# lightsensor.net
KiCad netlist of a schematic drawn in EAGLE
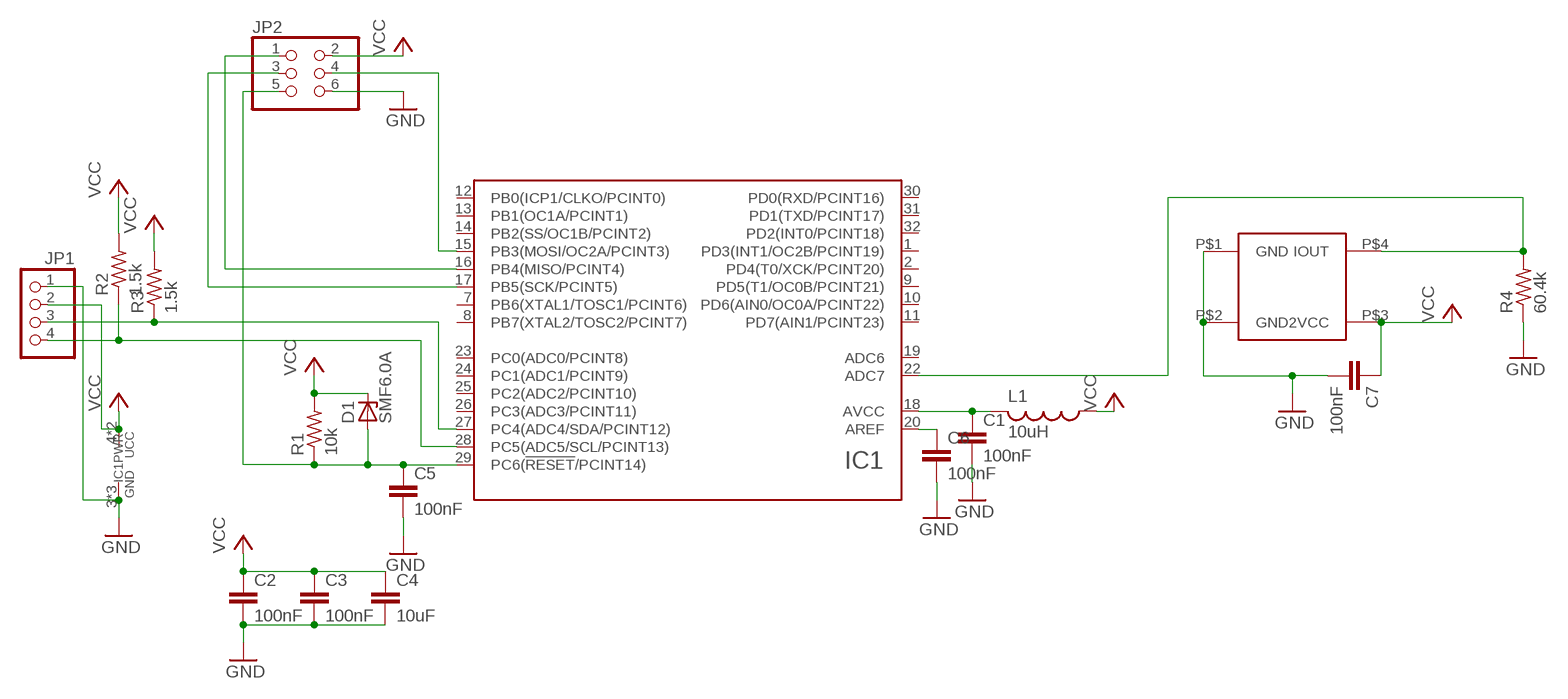
[diagram p0: schematic, sheet 1]

(export (version "E")
  (design (tool "Eeschema 10.0.6"))
  (components
    (comp (ref "C1")
      (value "100nF")
      (footprint "eagle-import:C0402")
      (libsource (lib "eagle-import") (part "C-EUC0402"))
    )
    (comp (ref "C2")
      (value "100nF")
      (footprint "eagle-import:C0402")
      (libsource (lib "eagle-import") (part "C-EUC0402"))
    )
    (comp (ref "C3")
      (value "100nF")
      (footprint "eagle-import:C0402")
      (libsource (lib "eagle-import") (part "C-EUC0402"))
    )
    (comp (ref "C4")
      (value "10uF")
      (footprint "eagle-import:C0603")
      (libsource (lib "eagle-import") (part "C-EUC0603"))
    )
    (comp (ref "C5")
      (value "100nF")
      (footprint "eagle-import:C0402")
      (libsource (lib "eagle-import") (part "C-EUC0402"))
    )
    (comp (ref "C6")
      (value "100nF")
      (footprint "eagle-import:C0402")
      (libsource (lib "eagle-import") (part "C-EUC0402"))
    )
    (comp (ref "C7")
      (value "100nF")
      (footprint "eagle-import:C0402")
      (libsource (lib "eagle-import") (part "C-EUC0402"))
    )
    (comp (ref "D1")
      (value "SMF6.0A")
      (footprint "eagle-import:SOD123F")
      (fields (field (name "MF") "Littelfuse"))
      (libsource (lib "eagle-import") (part "SMFA6.0"))
    )
    (comp (ref "IC1")
      (value "ATMEGA48/88/168/328-AU")
      (footprint "eagle-import:TQFP32-08")
      (libsource (lib "eagle-import") (part "ATMEGA48/88/168/328-AU"))
    )
    (comp (ref "JP1")
      (value "PINHD-1X4")
      (footprint "eagle-import:1X04")
      (libsource (lib "eagle-import") (part "PINHD-1X4"))
    )
    (comp (ref "JP2")
      (value "PINHD-2X3")
      (footprint "eagle-import:2X03")
      (libsource (lib "eagle-import") (part "PINHD-2X3"))
    )
    (comp (ref "L1")
      (value "10uH")
      (footprint "eagle-import:L2012C")
      (libsource (lib "eagle-import") (part "L-USL2012C"))
    )
    (comp (ref "R1")
      (value "10k")
      (footprint "eagle-import:R0402")
      (libsource (lib "eagle-import") (part "R-US_R0402"))
    )
    (comp (ref "R2")
      (value "1.5k")
      (footprint "eagle-import:R0402")
      (libsource (lib "eagle-import") (part "R-US_R0402"))
    )
    (comp (ref "R3")
      (value "1.5k")
      (footprint "eagle-import:R0402")
      (libsource (lib "eagle-import") (part "R-US_R0402"))
    )
    (comp (ref "R4")
      (value "60.4k")
      (footprint "eagle-import:R0603")
      (libsource (lib "eagle-import") (part "R-US_R0603"))
    )
    (comp (ref "U$1")
      (value "SFH5711")
      (footprint "eagle-import:SFH5711")
      (libsource (lib "eagle-import") (part "SFH5711"))
    )
  )
  (nets
    (net (code "1") (name "GND") (class "Default")
      (node (ref "C1") (pin "2") (pinfunction "2_2") (pintype "passive"))
      (node (ref "C2") (pin "2") (pinfunction "2_2") (pintype "passive"))
      (node (ref "C3") (pin "2") (pinfunction "2_2") (pintype "passive"))
      (node (ref "C4") (pin "2") (pinfunction "2_2") (pintype "passive"))
      (node (ref "C5") (pin "2") (pinfunction "2_2") (pintype "passive"))
      (node (ref "C6") (pin "2") (pinfunction "2_2") (pintype "passive"))
      (node (ref "C7") (pin "2") (pinfunction "2_2") (pintype "passive"))
      (node (ref "IC1") (pin "21") (pinfunction "GND_21") (pintype "power_in"))
      (node (ref "IC1") (pin "3") (pinfunction "GND_3") (pintype "power_in"))
      (node (ref "IC1") (pin "5") (pinfunction "GND_5") (pintype "power_in"))
      (node (ref "JP1") (pin "1") (pinfunction "1_1") (pintype "passive"))
      (node (ref "JP2") (pin "6") (pinfunction "6_6") (pintype "passive"))
      (node (ref "R4") (pin "1") (pinfunction "1_1") (pintype "passive"))
      (node (ref "U$1") (pin "P$1") (pinfunction "GND_P$1") (pintype "bidirectional"))
      (node (ref "U$1") (pin "P$2") (pinfunction "GND2_P$2") (pintype "bidirectional"))
    )
    (net (code "2") (name "Net-(IC1A-ADC7)") (class "Default")
      (node (ref "IC1") (pin "22") (pinfunction "ADC7_22") (pintype "passive"))
      (node (ref "R4") (pin "2") (pinfunction "2_2") (pintype "passive"))
      (node (ref "U$1") (pin "P$4") (pinfunction "IOUT_P$4") (pintype "bidirectional"))
    )
    (net (code "3") (name "Net-(IC1A-AREF)") (class "Default")
      (node (ref "C6") (pin "1") (pinfunction "1_1") (pintype "passive"))
      (node (ref "IC1") (pin "20") (pinfunction "AREF_20") (pintype "passive"))
    )
    (net (code "4") (name "Net-(IC1A-AVCC)") (class "Default")
      (node (ref "C1") (pin "1") (pinfunction "1_1") (pintype "passive"))
      (node (ref "IC1") (pin "18") (pinfunction "AVCC_18") (pintype "power_in"))
      (node (ref "L1") (pin "2") (pinfunction "2_2") (pintype "passive"))
    )
    (net (code "5") (name "Net-(IC1A-PB3(MOSI{slash}OC2A{slash}PCINT3))") (class "Default")
      (node (ref "IC1") (pin "15") (pinfunction "PB3(MOSI/OC2A/PCINT3)_15") (pintype "bidirectional"))
      (node (ref "JP2") (pin "4") (pinfunction "4_4") (pintype "passive"))
    )
    (net (code "6") (name "Net-(IC1A-PB4(MISO{slash}PCINT4))") (class "Default")
      (node (ref "IC1") (pin "16") (pinfunction "PB4(MISO/PCINT4)_16") (pintype "bidirectional"))
      (node (ref "JP2") (pin "1") (pinfunction "1_1") (pintype "passive"))
    )
    (net (code "7") (name "Net-(IC1A-PB5(SCK{slash}PCINT5))") (class "Default")
      (node (ref "IC1") (pin "17") (pinfunction "PB5(SCK/PCINT5)_17") (pintype "bidirectional"))
      (node (ref "JP2") (pin "3") (pinfunction "3_3") (pintype "passive"))
    )
    (net (code "8") (name "Net-(IC1A-PC4(ADC4{slash}SDA{slash}PCINT12))") (class "Default")
      (node (ref "IC1") (pin "27") (pinfunction "PC4(ADC4/SDA/PCINT12)_27") (pintype "bidirectional"))
      (node (ref "JP1") (pin "3") (pinfunction "3_3") (pintype "passive"))
      (node (ref "R3") (pin "1") (pinfunction "1_1") (pintype "passive"))
    )
    (net (code "9") (name "Net-(IC1A-PC5(ADC5{slash}SCL{slash}PCINT13))") (class "Default")
      (node (ref "IC1") (pin "28") (pinfunction "PC5(ADC5/SCL/PCINT13)_28") (pintype "bidirectional"))
      (node (ref "JP1") (pin "4") (pinfunction "4_4") (pintype "passive"))
      (node (ref "R2") (pin "1") (pinfunction "1_1") (pintype "passive"))
    )
    (net (code "10") (name "Net-(IC1A-PC6(~{RESET}{slash}PCINT14))") (class "Default")
      (node (ref "C5") (pin "1") (pinfunction "1_1") (pintype "passive"))
      (node (ref "D1") (pin "A") (pinfunction "A_A") (pintype "passive"))
      (node (ref "IC1") (pin "29") (pinfunction "PC6(~{RESET}/PCINT14)_29") (pintype "bidirectional"))
      (node (ref "JP2") (pin "5") (pinfunction "5_5") (pintype "passive"))
      (node (ref "R1") (pin "1") (pinfunction "1_1") (pintype "passive"))
    )
    (net (code "11") (name "VCC") (class "Default")
      (node (ref "C2") (pin "1") (pinfunction "1_1") (pintype "passive"))
      (node (ref "C3") (pin "1") (pinfunction "1_1") (pintype "passive"))
      (node (ref "C4") (pin "1") (pinfunction "1_1") (pintype "passive"))
      (node (ref "C7") (pin "1") (pinfunction "1_1") (pintype "passive"))
      (node (ref "D1") (pin "C") (pinfunction "C_C") (pintype "passive"))
      (node (ref "IC1") (pin "4") (pinfunction "UCC_4") (pintype "power_in"))
      (node (ref "IC1") (pin "6") (pinfunction "UCC_6") (pintype "power_in"))
      (node (ref "JP1") (pin "2") (pinfunction "2_2") (pintype "passive"))
      (node (ref "JP2") (pin "2") (pinfunction "2_2") (pintype "passive"))
      (node (ref "L1") (pin "1") (pinfunction "1_1") (pintype "passive"))
      (node (ref "R1") (pin "2") (pinfunction "2_2") (pintype "passive"))
      (node (ref "R2") (pin "2") (pinfunction "2_2") (pintype "passive"))
      (node (ref "R3") (pin "2") (pinfunction "2_2") (pintype "passive"))
      (node (ref "U$1") (pin "P$3") (pinfunction "VCC_P$3") (pintype "bidirectional"))
    )
    (net (code "12") (name "unconnected-(IC1A-ADC6-Pad19)") (class "Default")
      (node (ref "IC1") (pin "19") (pinfunction "ADC6_19") (pintype "passive"))
    )
    (net (code "13") (name "unconnected-(IC1A-PB0(ICP1{slash}CLKO{slash}PCINT0)-Pad12)") (class "Default")
      (node (ref "IC1") (pin "12") (pinfunction "PB0(ICP1/CLKO/PCINT0)_12") (pintype "bidirectional"))
    )
    (net (code "14") (name "unconnected-(IC1A-PB1(OC1A{slash}PCINT1)-Pad13)") (class "Default")
      (node (ref "IC1") (pin "13") (pinfunction "PB1(OC1A/PCINT1)_13") (pintype "bidirectional"))
    )
    (net (code "15") (name "unconnected-(IC1A-PB2(SS{slash}OC1B{slash}PCINT2)-Pad14)") (class "Default")
      (node (ref "IC1") (pin "14") (pinfunction "PB2(SS/OC1B/PCINT2)_14") (pintype "bidirectional"))
    )
    (net (code "16") (name "unconnected-(IC1A-PB6(XTAL1{slash}TOSC1{slash}PCINT6)-Pad7)") (class "Default")
      (node (ref "IC1") (pin "7") (pinfunction "PB6(XTAL1/TOSC1/PCINT6)_7") (pintype "bidirectional"))
    )
    (net (code "17") (name "unconnected-(IC1A-PB7(XTAL2{slash}TOSC2{slash}PCINT7)-Pad8)") (class "Default")
      (node (ref "IC1") (pin "8") (pinfunction "PB7(XTAL2/TOSC2/PCINT7)_8") (pintype "bidirectional"))
    )
    (net (code "18") (name "unconnected-(IC1A-PC0(ADC0{slash}PCINT8)-Pad23)") (class "Default")
      (node (ref "IC1") (pin "23") (pinfunction "PC0(ADC0/PCINT8)_23") (pintype "bidirectional"))
    )
    (net (code "19") (name "unconnected-(IC1A-PC1(ADC1{slash}PCINT9)-Pad24)") (class "Default")
      (node (ref "IC1") (pin "24") (pinfunction "PC1(ADC1/PCINT9)_24") (pintype "bidirectional"))
    )
    (net (code "20") (name "unconnected-(IC1A-PC2(ADC2{slash}PCINT10)-Pad25)") (class "Default")
      (node (ref "IC1") (pin "25") (pinfunction "PC2(ADC2/PCINT10)_25") (pintype "bidirectional"))
    )
    (net (code "21") (name "unconnected-(IC1A-PC3(ADC3{slash}PCINT11)-Pad26)") (class "Default")
      (node (ref "IC1") (pin "26") (pinfunction "PC3(ADC3/PCINT11)_26") (pintype "bidirectional"))
    )
    (net (code "22") (name "unconnected-(IC1A-PD0(RXD{slash}PCINT16)-Pad30)") (class "Default")
      (node (ref "IC1") (pin "30") (pinfunction "PD0(RXD/PCINT16)_30") (pintype "bidirectional"))
    )
    (net (code "23") (name "unconnected-(IC1A-PD1(TXD{slash}PCINT17)-Pad31)") (class "Default")
      (node (ref "IC1") (pin "31") (pinfunction "PD1(TXD/PCINT17)_31") (pintype "bidirectional"))
    )
    (net (code "24") (name "unconnected-(IC1A-PD2(INT0{slash}PCINT18)-Pad32)") (class "Default")
      (node (ref "IC1") (pin "32") (pinfunction "PD2(INT0/PCINT18)_32") (pintype "bidirectional"))
    )
    (net (code "25") (name "unconnected-(IC1A-PD3(INT1{slash}OC2B{slash}PCINT19)-Pad1)") (class "Default")
      (node (ref "IC1") (pin "1") (pinfunction "PD3(INT1/OC2B/PCINT19)_1") (pintype "bidirectional"))
    )
    (net (code "26") (name "unconnected-(IC1A-PD4(T0{slash}XCK{slash}PCINT20)-Pad2)") (class "Default")
      (node (ref "IC1") (pin "2") (pinfunction "PD4(T0/XCK/PCINT20)_2") (pintype "bidirectional"))
    )
    (net (code "27") (name "unconnected-(IC1A-PD5(T1{slash}OC0B{slash}PCINT21)-Pad9)") (class "Default")
      (node (ref "IC1") (pin "9") (pinfunction "PD5(T1/OC0B/PCINT21)_9") (pintype "bidirectional"))
    )
    (net (code "28") (name "unconnected-(IC1A-PD6(AIN0{slash}OC0A{slash}PCINT22)-Pad10)") (class "Default")
      (node (ref "IC1") (pin "10") (pinfunction "PD6(AIN0/OC0A/PCINT22)_10") (pintype "bidirectional"))
    )
    (net (code "29") (name "unconnected-(IC1A-PD7(AIN1{slash}PCINT23)-Pad11)") (class "Default")
      (node (ref "IC1") (pin "11") (pinfunction "PD7(AIN1/PCINT23)_11") (pintype "bidirectional"))
    )
  )
)
